# backplaneIGVC.net
KiCad netlist of a schematic drawn in Altium Designer
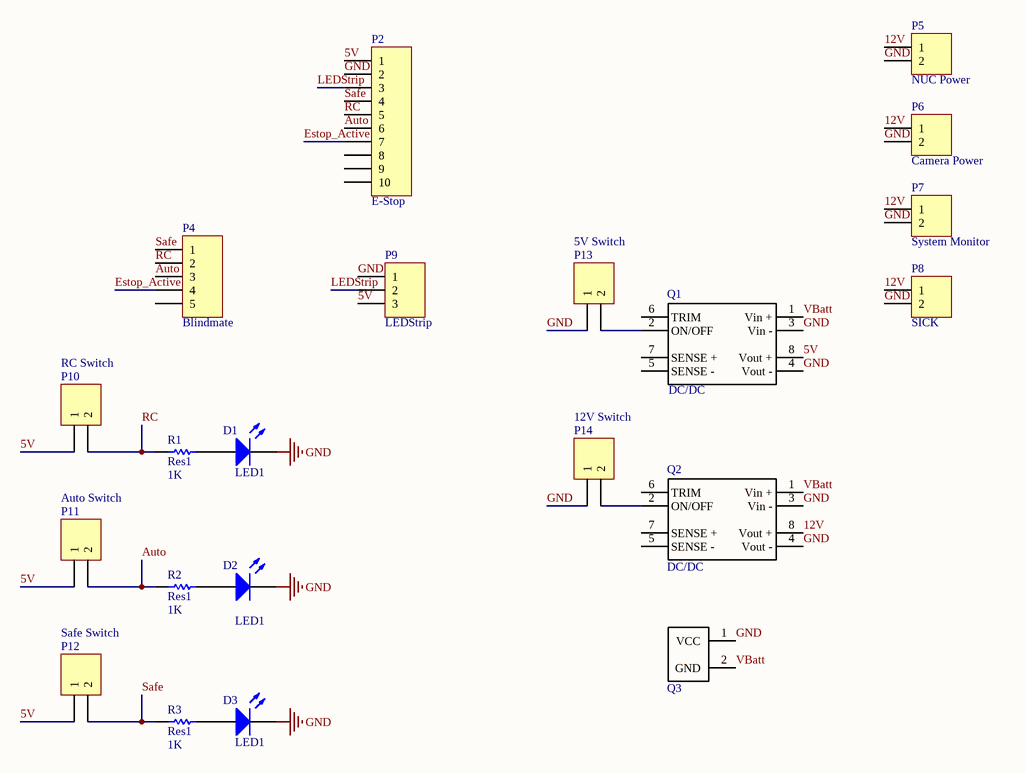
[diagram p0: backplaneIGVC.SchDoc]

(export (version "E")
  (design (tool "Eeschema 10.0.6"))
  (components
    (comp (ref "D1")
      (value "LED1")
      (footprint "LED-1")
      (description "Typical RED GaAs LED")
      (fields (field (name "PUBLISHER") "Altium Limited"))
      (libsource (lib "Miscellaneous Devices") (part "LED1"))
    )
    (comp (ref "D2")
      (value "LED1")
      (footprint "LED-1")
      (description "Typical RED GaAs LED")
      (fields (field (name "PUBLISHER") "Altium Limited"))
      (libsource (lib "Miscellaneous Devices") (part "LED1"))
    )
    (comp (ref "D3")
      (value "LED1")
      (footprint "LED-1")
      (description "Typical RED GaAs LED")
      (fields (field (name "PUBLISHER") "Altium Limited"))
      (libsource (lib "Miscellaneous Devices") (part "LED1"))
    )
    (comp (ref "P2")
      (value "E-Stop")
      (footprint "HDR1X10")
      (description "Header, 10-Pin")
      (fields (field (name "PUBLISHER") "Altium Limited"))
      (libsource (lib "Miscellaneous Connectors") (part "Header 10"))
    )
    (comp (ref "P4")
      (value "Blindmate")
      (footprint "HDR1X5")
      (description "Header, 5-Pin")
      (fields (field (name "PUBLISHER") "Altium Limited"))
      (libsource (lib "Miscellaneous Connectors") (part "Header 5"))
    )
    (comp (ref "P5")
      (value "NUC Power")
      (footprint "HDR1X2")
      (description "Header, 2-Pin")
      (fields (field (name "PUBLISHER") "Altium Limited"))
      (libsource (lib "") (part "Header 2_1"))
    )
    (comp (ref "P6")
      (value "Camera Power")
      (footprint "HDR1X2")
      (description "Header, 2-Pin")
      (fields (field (name "PUBLISHER") "Altium Limited"))
      (libsource (lib "") (part "Header 2_1"))
    )
    (comp (ref "P7")
      (value "System Monitor")
      (footprint "HDR1X2")
      (description "Header, 2-Pin")
      (fields (field (name "PUBLISHER") "Altium Limited"))
      (libsource (lib "") (part "Header 2_1"))
    )
    (comp (ref "P8")
      (value "SICK")
      (footprint "HDR1X2")
      (description "Header, 2-Pin")
      (fields (field (name "PUBLISHER") "Altium Limited"))
      (libsource (lib "") (part "Header 2_1"))
    )
    (comp (ref "P9")
      (value "LEDStrip")
      (footprint "HDR1X3")
      (description "Header, 3-Pin")
      (fields (field (name "PUBLISHER") "Altium Limited"))
      (libsource (lib "Miscellaneous Connectors") (part "Header 3"))
    )
    (comp (ref "P10")
      (value "RC Switch")
      (footprint "HDR1X2")
      (description "Header, 2-Pin")
      (fields (field (name "PUBLISHER") "Altium Limited"))
      (libsource (lib "Miscellaneous Connectors") (part "Header 2"))
    )
    (comp (ref "P11")
      (value "Auto Switch")
      (footprint "HDR1X2")
      (description "Header, 2-Pin")
      (fields (field (name "PUBLISHER") "Altium Limited"))
      (libsource (lib "Miscellaneous Connectors") (part "Header 2"))
    )
    (comp (ref "P12")
      (value "Safe Switch")
      (footprint "HDR1X2")
      (description "Header, 2-Pin")
      (fields (field (name "PUBLISHER") "Altium Limited"))
      (libsource (lib "Miscellaneous Connectors") (part "Header 2"))
    )
    (comp (ref "P13")
      (value "5V Switch")
      (footprint "HDR1X2")
      (description "Header, 2-Pin")
      (fields (field (name "PUBLISHER") "Altium Limited"))
      (libsource (lib "Miscellaneous Connectors") (part "Header 2"))
    )
    (comp (ref "P14")
      (value "12V Switch")
      (footprint "HDR1X2")
      (description "Header, 2-Pin")
      (fields (field (name "PUBLISHER") "Altium Limited"))
      (libsource (lib "Miscellaneous Connectors") (part "Header 2"))
    )
    (comp (ref "Q1")
      (value "DC/DC")
      (footprint "EHHD")
      (description "Voltage Regulator")
      (libsource (lib "Custom_Components") (part "EHHD"))
    )
    (comp (ref "Q2")
      (value "DC/DC")
      (footprint "EHHD")
      (description "Voltage Regulator")
      (libsource (lib "Custom_Components") (part "EHHD"))
    )
    (comp (ref "Q3")
      (value "Power Conn")
      (footprint "Mini-Fit Power Conn")
      (description "Mini-Fit Molex Connector")
      (libsource (lib "Custom_Components") (part "Mini-Fit Power Conn"))
    )
    (comp (ref "R1")
      (value "Res1")
      (footprint "AXIAL-0.3")
      (description "Resistor")
      (fields (field (name "ALTIUM_VALUE") "1K") (field (name "PUBLISHER") "Altium Limited"))
      (libsource (lib "Miscellaneous Devices") (part "Res1"))
    )
    (comp (ref "R2")
      (value "Res1")
      (footprint "AXIAL-0.3")
      (description "Resistor")
      (fields (field (name "ALTIUM_VALUE") "1K") (field (name "PUBLISHER") "Altium Limited"))
      (libsource (lib "Miscellaneous Devices") (part "Res1"))
    )
    (comp (ref "R3")
      (value "Res1")
      (footprint "AXIAL-0.3")
      (description "Resistor")
      (fields (field (name "ALTIUM_VALUE") "1K") (field (name "PUBLISHER") "Altium Limited"))
      (libsource (lib "Miscellaneous Devices") (part "Res1"))
    )
  )
  (nets
    (net (code "1") (name "/5V") (class "Default")
      (node (ref "P10") (pin "1") (pinfunction "1_1") (pintype "passive"))
      (node (ref "P11") (pin "1") (pinfunction "1_1") (pintype "passive"))
      (node (ref "P12") (pin "1") (pinfunction "1_1") (pintype "passive"))
      (node (ref "P2") (pin "1") (pinfunction "1_1") (pintype "passive"))
      (node (ref "P9") (pin "3") (pinfunction "3_3") (pintype "passive"))
      (node (ref "Q1") (pin "8") (pinfunction "Vout_+_8") (pintype "power_in"))
    )
    (net (code "2") (name "/12V") (class "Default")
      (node (ref "P5") (pin "1") (pinfunction "1_1") (pintype "passive"))
      (node (ref "P6") (pin "1") (pinfunction "1_1") (pintype "passive"))
      (node (ref "P7") (pin "1") (pinfunction "1_1") (pintype "passive"))
      (node (ref "P8") (pin "1") (pinfunction "1_1") (pintype "passive"))
      (node (ref "Q2") (pin "8") (pinfunction "Vout_+_8") (pintype "power_in"))
    )
    (net (code "3") (name "/Auto") (class "Default")
      (node (ref "P11") (pin "2") (pinfunction "2_2") (pintype "passive"))
      (node (ref "P2") (pin "6") (pinfunction "6_6") (pintype "passive"))
      (node (ref "P4") (pin "3") (pinfunction "3_3") (pintype "passive"))
      (node (ref "R2") (pin "1") (pinfunction "1_1") (pintype "passive"))
    )
    (net (code "4") (name "/Estop_Active") (class "Default")
      (node (ref "P2") (pin "7") (pinfunction "7_7") (pintype "passive"))
      (node (ref "P4") (pin "4") (pinfunction "4_4") (pintype "passive"))
    )
    (net (code "5") (name "/LEDStrip") (class "Default")
      (node (ref "P2") (pin "3") (pinfunction "3_3") (pintype "passive"))
      (node (ref "P9") (pin "2") (pinfunction "2_2") (pintype "passive"))
    )
    (net (code "6") (name "/RC") (class "Default")
      (node (ref "P10") (pin "2") (pinfunction "2_2") (pintype "passive"))
      (node (ref "P2") (pin "5") (pinfunction "5_5") (pintype "passive"))
      (node (ref "P4") (pin "2") (pinfunction "2_2") (pintype "passive"))
      (node (ref "R1") (pin "1") (pinfunction "1_1") (pintype "passive"))
    )
    (net (code "7") (name "/Safe") (class "Default")
      (node (ref "P12") (pin "2") (pinfunction "2_2") (pintype "passive"))
      (node (ref "P2") (pin "4") (pinfunction "4_4") (pintype "passive"))
      (node (ref "P4") (pin "1") (pinfunction "1_1") (pintype "passive"))
      (node (ref "R3") (pin "1") (pinfunction "1_1") (pintype "passive"))
    )
    (net (code "8") (name "/VBatt") (class "Default")
      (node (ref "Q1") (pin "1") (pinfunction "Vin_+_1") (pintype "passive"))
      (node (ref "Q2") (pin "1") (pinfunction "Vin_+_1") (pintype "passive"))
      (node (ref "Q3") (pin "2") (pinfunction "GND_2") (pintype "power_in"))
    )
    (net (code "9") (name "GND") (class "Default")
      (node (ref "D1") (pin "2") (pinfunction "K_2") (pintype "passive"))
      (node (ref "D2") (pin "2") (pinfunction "K_2") (pintype "passive"))
      (node (ref "D3") (pin "2") (pinfunction "K_2") (pintype "passive"))
      (node (ref "P13") (pin "1") (pinfunction "1_1") (pintype "passive"))
      (node (ref "P14") (pin "1") (pinfunction "1_1") (pintype "passive"))
      (node (ref "P2") (pin "2") (pinfunction "2_2") (pintype "passive"))
      (node (ref "P5") (pin "2") (pinfunction "2_2") (pintype "passive"))
      (node (ref "P6") (pin "2") (pinfunction "2_2") (pintype "passive"))
      (node (ref "P7") (pin "2") (pinfunction "2_2") (pintype "passive"))
      (node (ref "P8") (pin "2") (pinfunction "2_2") (pintype "passive"))
      (node (ref "P9") (pin "1") (pinfunction "1_1") (pintype "passive"))
      (node (ref "Q1") (pin "3") (pinfunction "Vin_-_3") (pintype "passive"))
      (node (ref "Q1") (pin "4") (pinfunction "Vout_-_4") (pintype "power_in"))
      (node (ref "Q2") (pin "3") (pinfunction "Vin_-_3") (pintype "passive"))
      (node (ref "Q2") (pin "4") (pinfunction "Vout_-_4") (pintype "power_in"))
      (node (ref "Q3") (pin "1") (pinfunction "VCC_1") (pintype "power_in"))
    )
    (net (code "10") (name "Net-(D1-A)") (class "Default")
      (node (ref "D1") (pin "1") (pinfunction "A_1") (pintype "passive"))
      (node (ref "R1") (pin "2") (pinfunction "2_2") (pintype "passive"))
    )
    (net (code "11") (name "Net-(D2-A)") (class "Default")
      (node (ref "D2") (pin "1") (pinfunction "A_1") (pintype "passive"))
      (node (ref "R2") (pin "2") (pinfunction "2_2") (pintype "passive"))
    )
    (net (code "12") (name "Net-(D3-A)") (class "Default")
      (node (ref "D3") (pin "1") (pinfunction "A_1") (pintype "passive"))
      (node (ref "R3") (pin "2") (pinfunction "2_2") (pintype "passive"))
    )
    (net (code "13") (name "Net-(Q1-ON{slash}OFF)") (class "Default")
      (node (ref "P13") (pin "2") (pinfunction "2_2") (pintype "passive"))
      (node (ref "Q1") (pin "2") (pinfunction "ON/OFF_2") (pintype "passive"))
    )
    (net (code "14") (name "Net-(Q2-ON{slash}OFF)") (class "Default")
      (node (ref "P14") (pin "2") (pinfunction "2_2") (pintype "passive"))
      (node (ref "Q2") (pin "2") (pinfunction "ON/OFF_2") (pintype "passive"))
    )
    (net (code "15") (name "unconnected-(P2-Pad8)") (class "Default")
      (node (ref "P2") (pin "8") (pinfunction "8_8") (pintype "passive"))
    )
    (net (code "16") (name "unconnected-(P2-Pad9)") (class "Default")
      (node (ref "P2") (pin "9") (pinfunction "9_9") (pintype "passive"))
    )
    (net (code "17") (name "unconnected-(P2-Pad10)") (class "Default")
      (node (ref "P2") (pin "10") (pinfunction "10_10") (pintype "passive"))
    )
    (net (code "18") (name "unconnected-(P4-Pad5)") (class "Default")
      (node (ref "P4") (pin "5") (pinfunction "5_5") (pintype "passive"))
    )
    (net (code "19") (name "unconnected-(Q1-SENSE_+-Pad7)") (class "Default")
      (node (ref "Q1") (pin "7") (pinfunction "SENSE_+_7") (pintype "passive"))
    )
    (net (code "20") (name "unconnected-(Q1-SENSE_--Pad5)") (class "Default")
      (node (ref "Q1") (pin "5") (pinfunction "SENSE_-_5") (pintype "passive"))
    )
    (net (code "21") (name "unconnected-(Q1-TRIM-Pad6)") (class "Default")
      (node (ref "Q1") (pin "6") (pinfunction "TRIM_6") (pintype "passive"))
    )
    (net (code "22") (name "unconnected-(Q2-SENSE_+-Pad7)") (class "Default")
      (node (ref "Q2") (pin "7") (pinfunction "SENSE_+_7") (pintype "passive"))
    )
    (net (code "23") (name "unconnected-(Q2-SENSE_--Pad5)") (class "Default")
      (node (ref "Q2") (pin "5") (pinfunction "SENSE_-_5") (pintype "passive"))
    )
    (net (code "24") (name "unconnected-(Q2-TRIM-Pad6)") (class "Default")
      (node (ref "Q2") (pin "6") (pinfunction "TRIM_6") (pintype "passive"))
    )
  )
)
